# IR_Remote.net
KiCad netlist of a schematic drawn in EAGLE
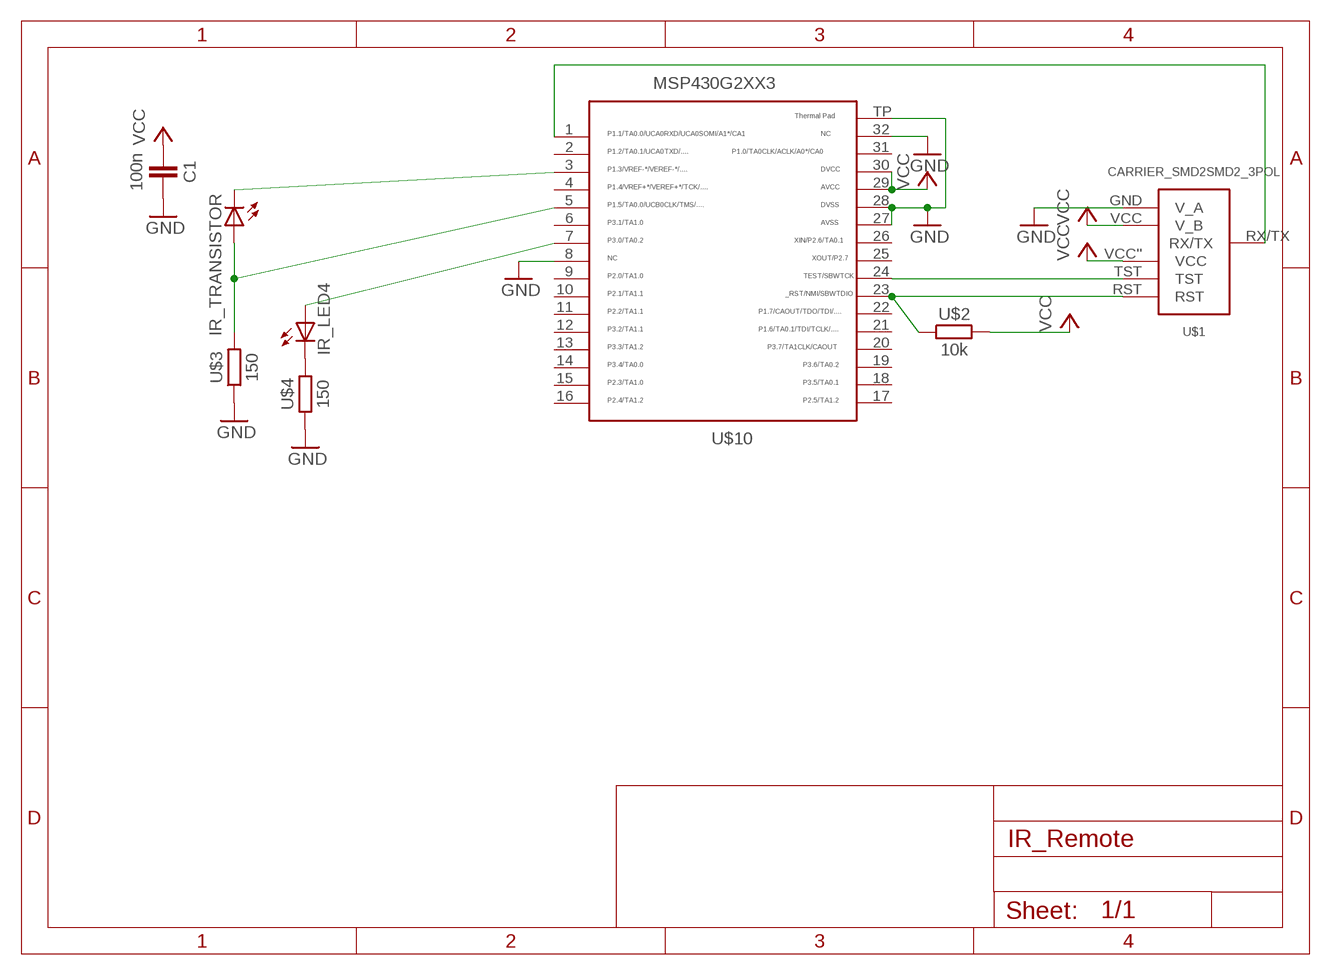
[diagram p0: schematic, sheet 1]

(export (version "E")
  (design (tool "Eeschema 10.0.6"))
  (components
    (comp (ref "C1")
      (value "100n")
      (footprint "eagle-import:603")
      (libsource (lib "eagle-import") (part "CAPACITOR"))
    )
    (comp (ref "IR_LED4")
      (value "LEDCHIP-LED0603")
      (footprint "eagle-import:CHIP-LED0603")
      (libsource (lib "eagle-import") (part "LEDCHIP-LED0603"))
    )
    (comp (ref "IR_TRANSISTOR")
      (value "LEDCHIP-LED0603")
      (footprint "eagle-import:CHIP-LED0603")
      (libsource (lib "eagle-import") (part "LEDCHIP-LED0603"))
    )
    (comp (ref "U$1")
      (value "CARRIER_SMD2SMD2_3POL")
      (footprint "eagle-import:CARRIER_SMD2_3POL")
      (libsource (lib "eagle-import") (part "CARRIER_SMD2SMD2_3POL"))
    )
    (comp (ref "U$2")
      (value "10k")
      (footprint "eagle-import:603")
      (libsource (lib "eagle-import") (part "RESISTOR0603"))
    )
    (comp (ref "U$3")
      (value "150")
      (footprint "eagle-import:603")
      (libsource (lib "eagle-import") (part "RESISTOR0603"))
    )
    (comp (ref "U$4")
      (value "150")
      (footprint "eagle-import:603")
      (libsource (lib "eagle-import") (part "RESISTOR0603"))
    )
    (comp (ref "U$10")
      (value "MSP430G2553")
      (footprint "eagle-import:QFN32")
      (libsource (lib "eagle-import") (part "MSP430G2553"))
    )
  )
  (nets
    (net (code "1") (name "GND") (class "Default")
      (node (ref "C1") (pin "2") (pinfunction "2_2") (pintype "passive"))
      (node (ref "U$1") (pin "GND") (pinfunction "V_A_GND") (pintype "bidirectional"))
      (node (ref "U$10") (pin "27") (pinfunction "27_27") (pintype "bidirectional"))
      (node (ref "U$10") (pin "28") (pinfunction "28_28") (pintype "bidirectional"))
      (node (ref "U$10") (pin "32") (pinfunction "32_32") (pintype "bidirectional"))
      (node (ref "U$10") (pin "8") (pinfunction "8_8") (pintype "bidirectional"))
      (node (ref "U$10") (pin "TP") (pinfunction "TP_TP") (pintype "bidirectional"))
      (node (ref "U$3") (pin "1") (pinfunction "1_1") (pintype "passive"))
      (node (ref "U$4") (pin "1") (pinfunction "1_1") (pintype "passive"))
    )
    (net (code "2") (name "Net-(IR_LED4-PadA)") (class "Default")
      (node (ref "IR_LED4") (pin "A") (pinfunction "A_A") (pintype "passive"))
      (node (ref "U$10") (pin "7") (pinfunction "7_7") (pintype "bidirectional"))
    )
    (net (code "3") (name "Net-(IR_LED4-PadC)") (class "Default")
      (node (ref "IR_LED4") (pin "C") (pinfunction "C_C") (pintype "passive"))
      (node (ref "U$4") (pin "2") (pinfunction "2_2") (pintype "passive"))
    )
    (net (code "4") (name "Net-(IR_TRANSISTOR-PadA)") (class "Default")
      (node (ref "IR_TRANSISTOR") (pin "A") (pinfunction "A_A") (pintype "passive"))
      (node (ref "U$10") (pin "5") (pinfunction "5_5") (pintype "bidirectional"))
      (node (ref "U$3") (pin "2") (pinfunction "2_2") (pintype "passive"))
    )
    (net (code "5") (name "Net-(IR_TRANSISTOR-PadC)") (class "Default")
      (node (ref "IR_TRANSISTOR") (pin "C") (pinfunction "C_C") (pintype "passive"))
      (node (ref "U$10") (pin "3") (pinfunction "3_3") (pintype "bidirectional"))
    )
    (net (code "6") (name "Net-(U$1-PadRST)") (class "Default")
      (node (ref "U$1") (pin "RST") (pinfunction "RST_RST") (pintype "bidirectional"))
      (node (ref "U$10") (pin "23") (pinfunction "23_23") (pintype "bidirectional"))
      (node (ref "U$2") (pin "1") (pinfunction "1_1") (pintype "passive"))
    )
    (net (code "7") (name "Net-(U$1-PadRX{slash}TX)") (class "Default")
      (node (ref "U$1") (pin "RX/TX") (pinfunction "RX/TX_RX/TX") (pintype "bidirectional"))
      (node (ref "U$10") (pin "1") (pinfunction "1_1") (pintype "bidirectional"))
    )
    (net (code "8") (name "Net-(U$1-PadTST)") (class "Default")
      (node (ref "U$1") (pin "TST") (pinfunction "TST_TST") (pintype "bidirectional"))
      (node (ref "U$10") (pin "24") (pinfunction "24_24") (pintype "bidirectional"))
    )
    (net (code "9") (name "VCC") (class "Default")
      (node (ref "C1") (pin "1") (pinfunction "1_1") (pintype "passive"))
      (node (ref "U$1") (pin "VCC") (pinfunction "V_B_VCC") (pintype "bidirectional"))
      (node (ref "U$1") (pin "VCC''") (pinfunction "VCC_VCC''") (pintype "bidirectional"))
      (node (ref "U$10") (pin "29") (pinfunction "29_29") (pintype "bidirectional"))
      (node (ref "U$10") (pin "30") (pinfunction "30_30") (pintype "bidirectional"))
      (node (ref "U$2") (pin "2") (pinfunction "2_2") (pintype "passive"))
    )
    (net (code "10") (name "unconnected-(U$10-Pad2)") (class "Default")
      (node (ref "U$10") (pin "2") (pinfunction "2_2") (pintype "bidirectional"))
    )
    (net (code "11") (name "unconnected-(U$10-Pad4)") (class "Default")
      (node (ref "U$10") (pin "4") (pinfunction "4_4") (pintype "bidirectional"))
    )
    (net (code "12") (name "unconnected-(U$10-Pad6)") (class "Default")
      (node (ref "U$10") (pin "6") (pinfunction "6_6") (pintype "bidirectional"))
    )
    (net (code "13") (name "unconnected-(U$10-Pad9)") (class "Default")
      (node (ref "U$10") (pin "9") (pinfunction "9_9") (pintype "bidirectional"))
    )
    (net (code "14") (name "unconnected-(U$10-Pad10)") (class "Default")
      (node (ref "U$10") (pin "10") (pinfunction "10_10") (pintype "bidirectional"))
    )
    (net (code "15") (name "unconnected-(U$10-Pad11)") (class "Default")
      (node (ref "U$10") (pin "11") (pinfunction "11_11") (pintype "bidirectional"))
    )
    (net (code "16") (name "unconnected-(U$10-Pad12)") (class "Default")
      (node (ref "U$10") (pin "12") (pinfunction "12_12") (pintype "bidirectional"))
    )
    (net (code "17") (name "unconnected-(U$10-Pad13)") (class "Default")
      (node (ref "U$10") (pin "13") (pinfunction "13_13") (pintype "bidirectional"))
    )
    (net (code "18") (name "unconnected-(U$10-Pad14)") (class "Default")
      (node (ref "U$10") (pin "14") (pinfunction "14_14") (pintype "bidirectional"))
    )
    (net (code "19") (name "unconnected-(U$10-Pad15)") (class "Default")
      (node (ref "U$10") (pin "15") (pinfunction "15_15") (pintype "bidirectional"))
    )
    (net (code "20") (name "unconnected-(U$10-Pad16)") (class "Default")
      (node (ref "U$10") (pin "16") (pinfunction "16_16") (pintype "bidirectional"))
    )
    (net (code "21") (name "unconnected-(U$10-Pad17)") (class "Default")
      (node (ref "U$10") (pin "17") (pinfunction "17_17") (pintype "bidirectional"))
    )
    (net (code "22") (name "unconnected-(U$10-Pad18)") (class "Default")
      (node (ref "U$10") (pin "18") (pinfunction "18_18") (pintype "bidirectional"))
    )
    (net (code "23") (name "unconnected-(U$10-Pad19)") (class "Default")
      (node (ref "U$10") (pin "19") (pinfunction "19_19") (pintype "bidirectional"))
    )
    (net (code "24") (name "unconnected-(U$10-Pad20)") (class "Default")
      (node (ref "U$10") (pin "20") (pinfunction "20_20") (pintype "bidirectional"))
    )
    (net (code "25") (name "unconnected-(U$10-Pad21)") (class "Default")
      (node (ref "U$10") (pin "21") (pinfunction "21_21") (pintype "bidirectional"))
    )
    (net (code "26") (name "unconnected-(U$10-Pad22)") (class "Default")
      (node (ref "U$10") (pin "22") (pinfunction "22_22") (pintype "bidirectional"))
    )
    (net (code "27") (name "unconnected-(U$10-Pad25)") (class "Default")
      (node (ref "U$10") (pin "25") (pinfunction "25_25") (pintype "bidirectional"))
    )
    (net (code "28") (name "unconnected-(U$10-Pad26)") (class "Default")
      (node (ref "U$10") (pin "26") (pinfunction "26_26") (pintype "bidirectional"))
    )
    (net (code "29") (name "unconnected-(U$10-Pad31)") (class "Default")
      (node (ref "U$10") (pin "31") (pinfunction "31_31") (pintype "bidirectional"))
    )
  )
)
